# AD8253.net
KiCad netlist of a schematic drawn in Altium Designer
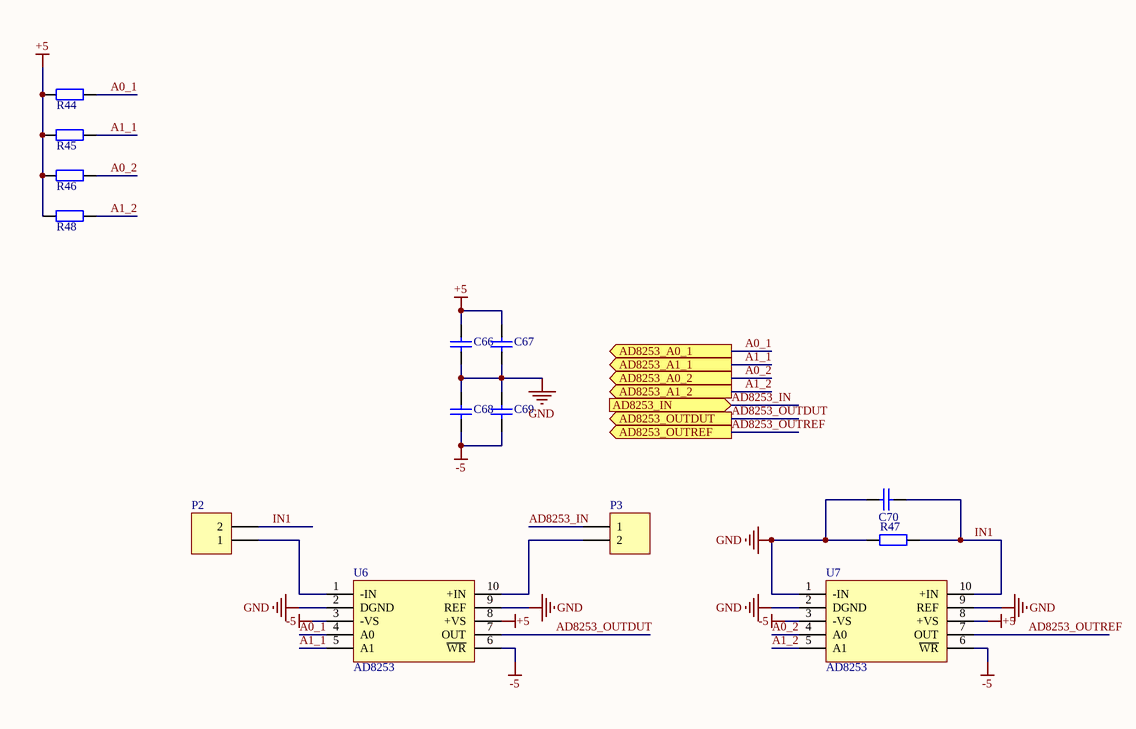
[diagram p0: AD8253.SchDoc]

(export (version "E")
  (design (tool "Eeschema 10.0.6"))
  (components
    (comp (ref "C66")
      (value "100nF (104) 10% 50V")
      (footprint "0603_C")
      (description "贴片电容")
      (libsource (lib "JLC") (part "0603 100nF (104) 10% 50V"))
    )
    (comp (ref "C67")
      (value "100nF (104) 10% 50V")
      (footprint "0603_C")
      (description "贴片电容")
      (libsource (lib "JLC") (part "0603 100nF (104) 10% 50V"))
    )
    (comp (ref "C68")
      (value "100nF (104) 10% 50V")
      (footprint "0603_C")
      (description "贴片电容")
      (libsource (lib "JLC") (part "0603 100nF (104) 10% 50V"))
    )
    (comp (ref "C69")
      (value "100nF (104) 10% 50V")
      (footprint "0603_C")
      (description "贴片电容")
      (libsource (lib "JLC") (part "0603 100nF (104) 10% 50V"))
    )
    (comp (ref "C70")
      (value "1.5nF (152) 10% 50V")
      (footprint "0603_C")
      (description "贴片电容")
      (libsource (lib "JLC") (part "0603 1.5nF (152) 10% 50V"))
    )
    (comp (ref "P2")
      (value "PORT_Header 2")
      (footprint "tow_pad_top")
      (description "Header, 2-Pin")
      (fields (field (name "PUBLISHER") "Altium Limited"))
      (libsource (lib "") (part "PORT_Header 2_1"))
    )
    (comp (ref "P3")
      (value "PORT_Header 2")
      (footprint "tow_pad_top")
      (description "Header, 2-Pin")
      (fields (field (name "PUBLISHER") "Altium Limited"))
      (libsource (lib "Cooperation") (part "PORT_Header 2"))
    )
    (comp (ref "R44")
      (value "110Ω (1100) ±1%")
      (footprint "0603_R")
      (description "贴片电阻")
      (libsource (lib "") (part "0603 110Ω (1100) 1%_1"))
    )
    (comp (ref "R45")
      (value "110Ω (1100) ±1%")
      (footprint "0603_R")
      (description "贴片电阻")
      (libsource (lib "") (part "0603 110Ω (1100) 1%_1"))
    )
    (comp (ref "R46")
      (value "110Ω (1100) ±1%")
      (footprint "0603_R")
      (description "贴片电阻")
      (libsource (lib "") (part "0603 110Ω (1100) 1%_1"))
    )
    (comp (ref "R47")
      (value "110Ω (1100) ±1%")
      (footprint "0603_R")
      (description "贴片电阻")
      (libsource (lib "JLC") (part "0603 110Ω (1100) 1%"))
    )
    (comp (ref "R48")
      (value "110Ω (1100) ±1%")
      (footprint "0603_R")
      (description "贴片电阻")
      (libsource (lib "") (part "0603 110Ω (1100) 1%_1"))
    )
    (comp (ref "U6") (value "AD8253") (footprint "MSOP10_M") (libsource (lib "Cooperation") (part "AD8253")))
    (comp (ref "U7") (value "AD8253") (footprint "MSOP10_M") (libsource (lib "Cooperation") (part "AD8253")))
  )
  (nets
    (net (code "1") (name "+5") (class "Default")
      (node (ref "C66") (pin "2") (pinfunction "2_2") (pintype "passive"))
      (node (ref "C67") (pin "2") (pinfunction "2_2") (pintype "passive"))
      (node (ref "R44") (pin "2") (pinfunction "2_2") (pintype "passive"))
      (node (ref "R45") (pin "2") (pinfunction "2_2") (pintype "passive"))
      (node (ref "R46") (pin "2") (pinfunction "2_2") (pintype "passive"))
      (node (ref "R48") (pin "2") (pinfunction "2_2") (pintype "passive"))
      (node (ref "U6") (pin "8") (pinfunction "+VS_8") (pintype "passive"))
      (node (ref "U7") (pin "8") (pinfunction "+VS_8") (pintype "passive"))
    )
    (net (code "2") (name "-5") (class "Default")
      (node (ref "C68") (pin "1") (pinfunction "1_1") (pintype "passive"))
      (node (ref "C69") (pin "1") (pinfunction "1_1") (pintype "passive"))
      (node (ref "U6") (pin "3") (pinfunction "-VS_3") (pintype "passive"))
      (node (ref "U6") (pin "6") (pinfunction "~{WR}_6") (pintype "passive"))
      (node (ref "U7") (pin "3") (pinfunction "-VS_3") (pintype "passive"))
      (node (ref "U7") (pin "6") (pinfunction "~{WR}_6") (pintype "passive"))
    )
    (net (code "3") (name "/A0_1") (class "Default")
      (node (ref "R44") (pin "1") (pinfunction "1_1") (pintype "passive"))
      (node (ref "U6") (pin "4") (pinfunction "A0_4") (pintype "passive"))
    )
    (net (code "4") (name "/A0_2") (class "Default")
      (node (ref "R46") (pin "1") (pinfunction "1_1") (pintype "passive"))
      (node (ref "U7") (pin "4") (pinfunction "A0_4") (pintype "passive"))
    )
    (net (code "5") (name "/A1_1") (class "Default")
      (node (ref "R45") (pin "1") (pinfunction "1_1") (pintype "passive"))
      (node (ref "U6") (pin "5") (pinfunction "A1_5") (pintype "passive"))
    )
    (net (code "6") (name "/A1_2") (class "Default")
      (node (ref "R48") (pin "1") (pinfunction "1_1") (pintype "passive"))
      (node (ref "U7") (pin "5") (pinfunction "A1_5") (pintype "passive"))
    )
    (net (code "7") (name "/AD8253_IN") (class "Default")
      (node (ref "P3") (pin "1") (pinfunction "1_1") (pintype "passive"))
    )
    (net (code "8") (name "/AD8253_OUTDUT") (class "Default")
      (node (ref "U6") (pin "7") (pinfunction "OUT_7") (pintype "passive"))
    )
    (net (code "9") (name "/AD8253_OUTREF") (class "Default")
      (node (ref "U7") (pin "7") (pinfunction "OUT_7") (pintype "passive"))
    )
    (net (code "10") (name "/IN1") (class "Default")
      (node (ref "C70") (pin "1") (pinfunction "1_1") (pintype "passive"))
      (node (ref "P2") (pin "2") (pinfunction "2_2") (pintype "passive"))
      (node (ref "R47") (pin "2") (pinfunction "2_2") (pintype "passive"))
      (node (ref "U7") (pin "10") (pinfunction "+IN_10") (pintype "passive"))
    )
    (net (code "11") (name "GND") (class "Default")
      (node (ref "C66") (pin "1") (pinfunction "1_1") (pintype "passive"))
      (node (ref "C67") (pin "1") (pinfunction "1_1") (pintype "passive"))
      (node (ref "C68") (pin "2") (pinfunction "2_2") (pintype "passive"))
      (node (ref "C69") (pin "2") (pinfunction "2_2") (pintype "passive"))
      (node (ref "C70") (pin "2") (pinfunction "2_2") (pintype "passive"))
      (node (ref "R47") (pin "1") (pinfunction "1_1") (pintype "passive"))
      (node (ref "U6") (pin "2") (pinfunction "DGND_2") (pintype "passive"))
      (node (ref "U6") (pin "9") (pinfunction "REF_9") (pintype "passive"))
      (node (ref "U7") (pin "1") (pinfunction "-IN_1") (pintype "passive"))
      (node (ref "U7") (pin "2") (pinfunction "DGND_2") (pintype "passive"))
      (node (ref "U7") (pin "9") (pinfunction "REF_9") (pintype "passive"))
    )
    (net (code "12") (name "Net-(U6-+IN)") (class "Default")
      (node (ref "P3") (pin "2") (pinfunction "2_2") (pintype "passive"))
      (node (ref "U6") (pin "10") (pinfunction "+IN_10") (pintype "passive"))
    )
    (net (code "13") (name "Net-(U6--IN)") (class "Default")
      (node (ref "P2") (pin "1") (pinfunction "1_1") (pintype "passive"))
      (node (ref "U6") (pin "1") (pinfunction "-IN_1") (pintype "passive"))
    )
  )
)
